# ow_lcd_mirror3.net
KiCad netlist of a schematic drawn in EAGLE
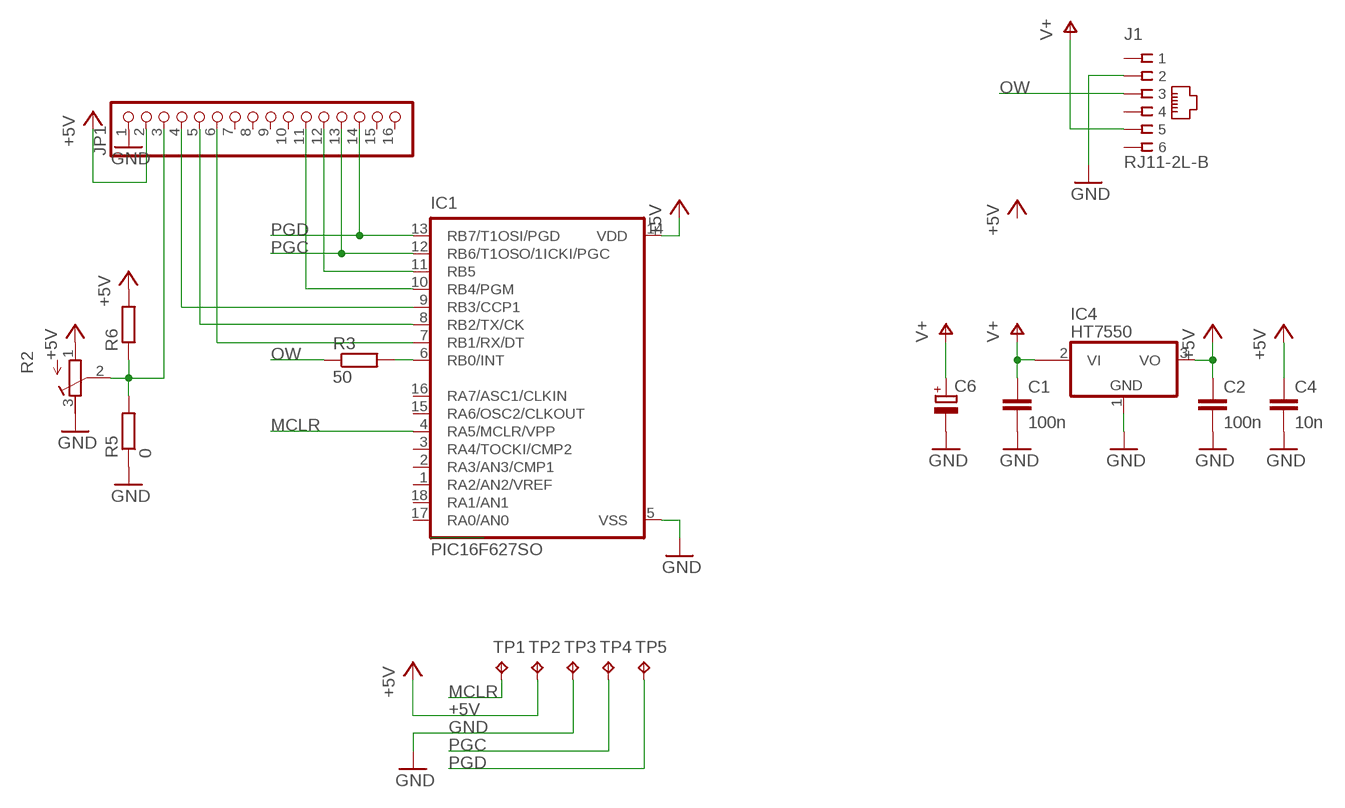
[diagram p0: schematic, sheet 1]

(export (version "E")
  (design (tool "Eeschema 10.0.6"))
  (components
    (comp (ref "C1")
      (value "100n")
      (footprint "eagle-import:C1206")
      (libsource (lib "eagle-import") (part "C-EUC1206"))
    )
    (comp (ref "C2")
      (value "100n")
      (footprint "eagle-import:C1206")
      (libsource (lib "eagle-import") (part "C-EUC1206"))
    )
    (comp (ref "C4")
      (value "10n")
      (footprint "eagle-import:C1206")
      (libsource (lib "eagle-import") (part "C-EUC1206"))
    )
    (comp (ref "C6")
      (value "CPOL-EUC/6032-28R")
      (footprint "eagle-import:C_6032-28R")
      (libsource (lib "eagle-import") (part "CPOL-EUC/6032-28R"))
    )
    (comp (ref "IC1")
      (value "PIC16F627SO")
      (footprint "eagle-import:SO-18W")
      (fields (field (name "MF") "MICROCHIP") (field (name "MPN") "PIC16F627-04/SO"))
      (libsource (lib "eagle-import") (part "PIC16F627SO"))
    )
    (comp (ref "IC4")
      (value "HT7550")
      (footprint "eagle-import:SOT89")
      (libsource (lib "eagle-import") (part "MCP1703MB12"))
    )
    (comp (ref "J1")
      (value "RJ11-2L-B")
      (footprint "eagle-import:RJ11-NO_SHIELD")
      (fields (field (name "MF") "TYCO ELECTRONICS"))
      (libsource (lib "eagle-import") (part "RJ11-2L-B"))
    )
    (comp (ref "JP1")
      (value "PINHD-1X16")
      (footprint "eagle-import:1X16")
      (libsource (lib "eagle-import") (part "PINHD-1X16"))
    )
    (comp (ref "R2")
      (value "R-TRIMM3339P")
      (footprint "eagle-import:RTRIM3339P")
      (libsource (lib "eagle-import") (part "R-TRIMM3339P"))
    )
    (comp (ref "R3")
      (value "50")
      (footprint "eagle-import:M1206")
      (libsource (lib "eagle-import") (part "resistor_R-EU_M1206"))
    )
    (comp (ref "R5")
      (value "0")
      (footprint "eagle-import:R0805")
      (libsource (lib "eagle-import") (part "R-EU_R0805"))
    )
    (comp (ref "R6")
      (value "R-EU_R0805")
      (footprint "eagle-import:R0805")
      (libsource (lib "eagle-import") (part "R-EU_R0805"))
    )
    (comp (ref "TP1")
      (value "TPB1,27")
      (footprint "eagle-import:B1,27")
      (libsource (lib "eagle-import") (part "TPB1,27"))
    )
    (comp (ref "TP2")
      (value "TPB1,27")
      (footprint "eagle-import:B1,27")
      (libsource (lib "eagle-import") (part "TPB1,27"))
    )
    (comp (ref "TP3")
      (value "TPB1,27")
      (footprint "eagle-import:B1,27")
      (libsource (lib "eagle-import") (part "TPB1,27"))
    )
    (comp (ref "TP4")
      (value "TPB1,27")
      (footprint "eagle-import:B1,27")
      (libsource (lib "eagle-import") (part "TPB1,27"))
    )
    (comp (ref "TP5")
      (value "TPB1,27")
      (footprint "eagle-import:B1,27")
      (libsource (lib "eagle-import") (part "TPB1,27"))
    )
  )
  (nets
    (net (code "1") (name "+5V") (class "Default")
      (node (ref "C2") (pin "1") (pinfunction "1_1") (pintype "passive"))
      (node (ref "C4") (pin "1") (pinfunction "1_1") (pintype "passive"))
      (node (ref "IC1") (pin "14") (pinfunction "VDD_14") (pintype "power_in"))
      (node (ref "IC4") (pin "3") (pinfunction "VO_3") (pintype "passive"))
      (node (ref "JP1") (pin "2") (pinfunction "2_2") (pintype "passive"))
      (node (ref "R2") (pin "1") (pinfunction "E_1") (pintype "passive"))
      (node (ref "R6") (pin "2") (pinfunction "2_2") (pintype "passive"))
      (node (ref "TP2") (pin "TP") (pinfunction "TP_TP") (pintype "input"))
    )
    (net (code "2") (name "/MCLR") (class "Default")
      (node (ref "IC1") (pin "4") (pinfunction "RA5/MCLR/VPP_4") (pintype "input"))
      (node (ref "TP1") (pin "TP") (pinfunction "TP_TP") (pintype "input"))
    )
    (net (code "3") (name "/OW") (class "Default")
      (node (ref "J1") (pin "3") (pinfunction "3_3") (pintype "passive"))
      (node (ref "R3") (pin "1") (pinfunction "1_1") (pintype "passive"))
    )
    (net (code "4") (name "/PGC") (class "Default")
      (node (ref "IC1") (pin "12") (pinfunction "RB6/T1OSO/1ICKI/PGC_12") (pintype "bidirectional"))
      (node (ref "JP1") (pin "13") (pinfunction "13_13") (pintype "passive"))
      (node (ref "TP4") (pin "TP") (pinfunction "TP_TP") (pintype "input"))
    )
    (net (code "5") (name "/PGD") (class "Default")
      (node (ref "IC1") (pin "13") (pinfunction "RB7/T1OSI/PGD_13") (pintype "bidirectional"))
      (node (ref "JP1") (pin "14") (pinfunction "14_14") (pintype "passive"))
      (node (ref "TP5") (pin "TP") (pinfunction "TP_TP") (pintype "input"))
    )
    (net (code "6") (name "GND") (class "Default")
      (node (ref "C1") (pin "2") (pinfunction "2_2") (pintype "passive"))
      (node (ref "C2") (pin "2") (pinfunction "2_2") (pintype "passive"))
      (node (ref "C4") (pin "2") (pinfunction "2_2") (pintype "passive"))
      (node (ref "C6") (pin "-") (pinfunction "-_-") (pintype "passive"))
      (node (ref "IC1") (pin "5") (pinfunction "VSS_5") (pintype "power_in"))
      (node (ref "IC4") (pin "1") (pinfunction "GND_1") (pintype "passive"))
      (node (ref "J1") (pin "2") (pinfunction "2_2") (pintype "passive"))
      (node (ref "JP1") (pin "1") (pinfunction "1_1") (pintype "passive"))
      (node (ref "R2") (pin "3") (pinfunction "A_3") (pintype "passive"))
      (node (ref "R5") (pin "1") (pinfunction "1_1") (pintype "passive"))
      (node (ref "TP3") (pin "TP") (pinfunction "TP_TP") (pintype "input"))
    )
    (net (code "7") (name "Net-(IC1-RB0{slash}INT)") (class "Default")
      (node (ref "IC1") (pin "6") (pinfunction "RB0/INT_6") (pintype "bidirectional"))
      (node (ref "R3") (pin "2") (pinfunction "2_2") (pintype "passive"))
    )
    (net (code "8") (name "Net-(IC1-RB1{slash}RX{slash}DT)") (class "Default")
      (node (ref "IC1") (pin "7") (pinfunction "RB1/RX/DT_7") (pintype "bidirectional"))
      (node (ref "JP1") (pin "6") (pinfunction "6_6") (pintype "passive"))
    )
    (net (code "9") (name "Net-(IC1-RB2{slash}TX{slash}CK)") (class "Default")
      (node (ref "IC1") (pin "8") (pinfunction "RB2/TX/CK_8") (pintype "bidirectional"))
      (node (ref "JP1") (pin "5") (pinfunction "5_5") (pintype "passive"))
    )
    (net (code "10") (name "Net-(IC1-RB3{slash}CCP1)") (class "Default")
      (node (ref "IC1") (pin "9") (pinfunction "RB3/CCP1_9") (pintype "bidirectional"))
      (node (ref "JP1") (pin "4") (pinfunction "4_4") (pintype "passive"))
    )
    (net (code "11") (name "Net-(IC1-RB4{slash}PGM)") (class "Default")
      (node (ref "IC1") (pin "10") (pinfunction "RB4/PGM_10") (pintype "bidirectional"))
      (node (ref "JP1") (pin "11") (pinfunction "11_11") (pintype "passive"))
    )
    (net (code "12") (name "Net-(IC1-RB5)") (class "Default")
      (node (ref "IC1") (pin "11") (pinfunction "RB5_11") (pintype "bidirectional"))
      (node (ref "JP1") (pin "12") (pinfunction "12_12") (pintype "passive"))
    )
    (net (code "13") (name "Net-(R2-S)") (class "Default")
      (node (ref "JP1") (pin "3") (pinfunction "3_3") (pintype "passive"))
      (node (ref "R2") (pin "2") (pinfunction "S_2") (pintype "passive"))
      (node (ref "R5") (pin "2") (pinfunction "2_2") (pintype "passive"))
      (node (ref "R6") (pin "1") (pinfunction "1_1") (pintype "passive"))
    )
    (net (code "14") (name "V+") (class "Default")
      (node (ref "C1") (pin "1") (pinfunction "1_1") (pintype "passive"))
      (node (ref "C6") (pin "+") (pinfunction "+_+") (pintype "passive"))
      (node (ref "IC4") (pin "2@1") (pinfunction "VI1_2@1") (pintype "input"))
      (node (ref "J1") (pin "5") (pinfunction "5_5") (pintype "passive"))
    )
    (net (code "15") (name "unconnected-(IC1-RA0{slash}AN0-Pad17)") (class "Default")
      (node (ref "IC1") (pin "17") (pinfunction "RA0/AN0_17") (pintype "bidirectional"))
    )
    (net (code "16") (name "unconnected-(IC1-RA1{slash}AN1-Pad18)") (class "Default")
      (node (ref "IC1") (pin "18") (pinfunction "RA1/AN1_18") (pintype "bidirectional"))
    )
    (net (code "17") (name "unconnected-(IC1-RA2{slash}AN2{slash}VREF-Pad1)") (class "Default")
      (node (ref "IC1") (pin "1") (pinfunction "RA2/AN2/VREF_1") (pintype "bidirectional"))
    )
    (net (code "18") (name "unconnected-(IC1-RA3{slash}AN3{slash}CMP1-Pad2)") (class "Default")
      (node (ref "IC1") (pin "2") (pinfunction "RA3/AN3/CMP1_2") (pintype "bidirectional"))
    )
    (net (code "19") (name "unconnected-(IC1-RA4{slash}TOCKI{slash}CMP2-Pad3)") (class "Default")
      (node (ref "IC1") (pin "3") (pinfunction "RA4/TOCKI/CMP2_3") (pintype "bidirectional"))
    )
    (net (code "20") (name "unconnected-(IC1-RA6{slash}OSC2{slash}CLKOUT-Pad15)") (class "Default")
      (node (ref "IC1") (pin "15") (pinfunction "RA6/OSC2/CLKOUT_15") (pintype "bidirectional"))
    )
    (net (code "21") (name "unconnected-(IC1-RA7{slash}ASC1{slash}CLKIN-Pad16)") (class "Default")
      (node (ref "IC1") (pin "16") (pinfunction "RA7/ASC1/CLKIN_16") (pintype "bidirectional"))
    )
    (net (code "22") (name "unconnected-(IC4-VI-Pad2)") (class "Default")
      (node (ref "IC4") (pin "2") (pinfunction "VI_2") (pintype "input"))
    )
    (net (code "23") (name "unconnected-(J1-Pad1)") (class "Default")
      (node (ref "J1") (pin "1") (pinfunction "1_1") (pintype "passive"))
    )
    (net (code "24") (name "unconnected-(J1-Pad4)") (class "Default")
      (node (ref "J1") (pin "4") (pinfunction "4_4") (pintype "passive"))
    )
    (net (code "25") (name "unconnected-(J1-Pad6)") (class "Default")
      (node (ref "J1") (pin "6") (pinfunction "6_6") (pintype "passive"))
    )
    (net (code "26") (name "unconnected-(JP1-Pad7)") (class "Default")
      (node (ref "JP1") (pin "7") (pinfunction "7_7") (pintype "passive"))
    )
    (net (code "27") (name "unconnected-(JP1-Pad8)") (class "Default")
      (node (ref "JP1") (pin "8") (pinfunction "8_8") (pintype "passive"))
    )
    (net (code "28") (name "unconnected-(JP1-Pad9)") (class "Default")
      (node (ref "JP1") (pin "9") (pinfunction "9_9") (pintype "passive"))
    )
    (net (code "29") (name "unconnected-(JP1-Pad10)") (class "Default")
      (node (ref "JP1") (pin "10") (pinfunction "10_10") (pintype "passive"))
    )
    (net (code "30") (name "unconnected-(JP1-Pad15)") (class "Default")
      (node (ref "JP1") (pin "15") (pinfunction "15_15") (pintype "passive"))
    )
    (net (code "31") (name "unconnected-(JP1-Pad16)") (class "Default")
      (node (ref "JP1") (pin "16") (pinfunction "16_16") (pintype "passive"))
    )
  )
)
